# pressure_foot.net
KiCad netlist of a schematic drawn in EAGLE
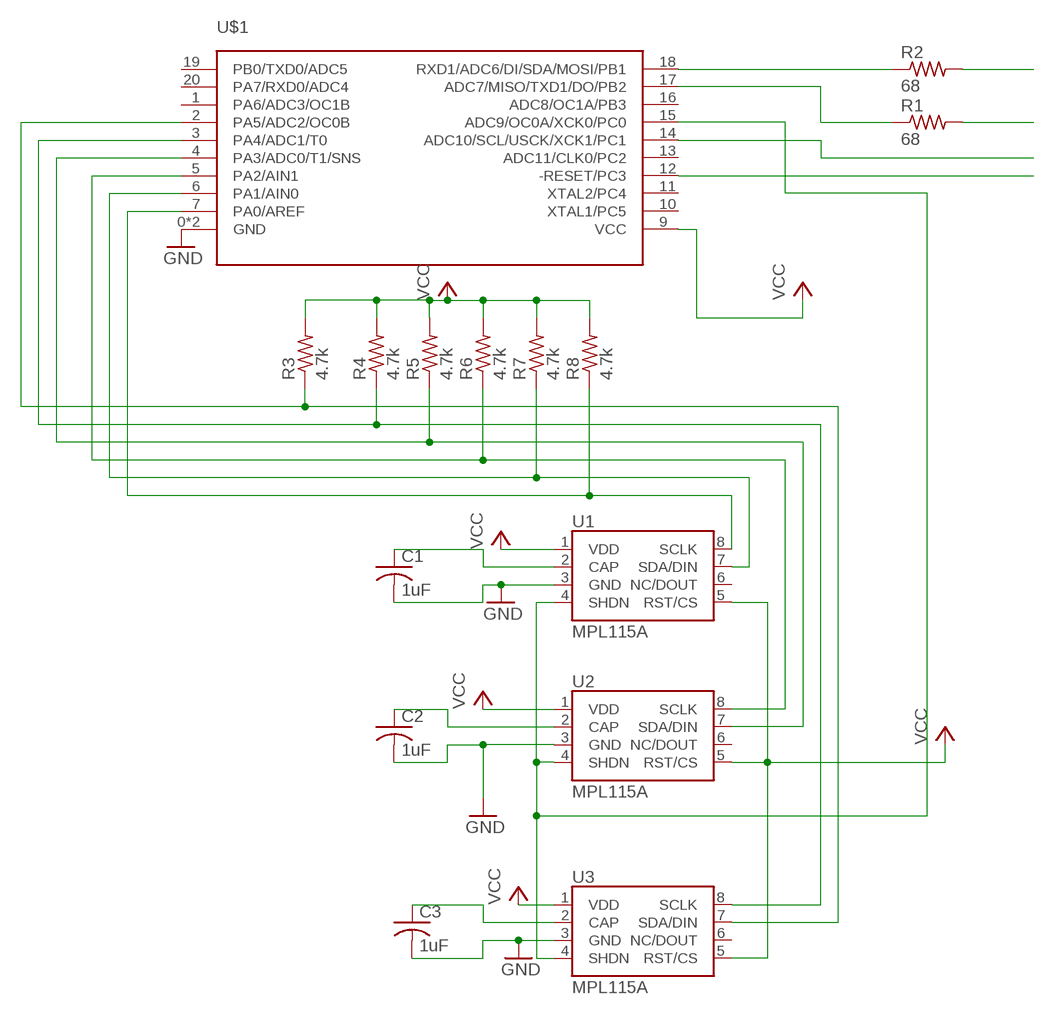
[diagram p0: schematic, sheet 1]

(export (version "E")
  (design (tool "Eeschema 10.0.6"))
  (components
    (comp (ref "C1")
      (value "1uF")
      (footprint "eagle-import:C0603")
      (libsource (lib "eagle-import") (part "C-USC0603"))
    )
    (comp (ref "C2")
      (value "1uF")
      (footprint "eagle-import:C0603")
      (libsource (lib "eagle-import") (part "C-USC0603"))
    )
    (comp (ref "C3")
      (value "1uF")
      (footprint "eagle-import:C0603")
      (libsource (lib "eagle-import") (part "C-USC0603"))
    )
    (comp (ref "R1")
      (value "68")
      (footprint "eagle-import:R0603")
      (libsource (lib "eagle-import") (part "R-US_R0603"))
    )
    (comp (ref "R2")
      (value "68")
      (footprint "eagle-import:R0603")
      (libsource (lib "eagle-import") (part "R-US_R0603"))
    )
    (comp (ref "R3")
      (value "4.7k")
      (footprint "eagle-import:R0603")
      (libsource (lib "eagle-import") (part "R-US_R0603"))
    )
    (comp (ref "R4")
      (value "4.7k")
      (footprint "eagle-import:R0603")
      (libsource (lib "eagle-import") (part "R-US_R0603"))
    )
    (comp (ref "R5")
      (value "4.7k")
      (footprint "eagle-import:R0603")
      (libsource (lib "eagle-import") (part "R-US_R0603"))
    )
    (comp (ref "R6")
      (value "4.7k")
      (footprint "eagle-import:R0603")
      (libsource (lib "eagle-import") (part "R-US_R0603"))
    )
    (comp (ref "R7")
      (value "4.7k")
      (footprint "eagle-import:R0603")
      (libsource (lib "eagle-import") (part "R-US_R0603"))
    )
    (comp (ref "R8")
      (value "4.7k")
      (footprint "eagle-import:R0603")
      (libsource (lib "eagle-import") (part "R-US_R0603"))
    )
    (comp (ref "U$1")
      (value "ATTINY1634QFN20")
      (footprint "eagle-import:QFN20")
      (libsource (lib "eagle-import") (part "ATTINY1634QFN20"))
    )
    (comp (ref "U1")
      (value "MPL115A")
      (footprint "eagle-import:LGA8")
      (libsource (lib "eagle-import") (part "MPL115A"))
    )
    (comp (ref "U2")
      (value "MPL115A")
      (footprint "eagle-import:LGA8")
      (libsource (lib "eagle-import") (part "MPL115A"))
    )
    (comp (ref "U3")
      (value "MPL115A")
      (footprint "eagle-import:LGA8")
      (libsource (lib "eagle-import") (part "MPL115A"))
    )
  )
  (nets
    (net (code "1") (name "GND") (class "Default")
      (node (ref "C1") (pin "2") (pinfunction "2_2") (pintype "passive"))
      (node (ref "C2") (pin "2") (pinfunction "2_2") (pintype "passive"))
      (node (ref "C3") (pin "2") (pinfunction "2_2") (pintype "passive"))
      (node (ref "U$1") (pin "0") (pinfunction "GND_0") (pintype "power_in"))
      (node (ref "U$1") (pin "8") (pinfunction "GND_8") (pintype "power_in"))
      (node (ref "U1") (pin "3") (pinfunction "GND_3") (pintype "bidirectional"))
      (node (ref "U2") (pin "3") (pinfunction "GND_3") (pintype "bidirectional"))
      (node (ref "U3") (pin "3") (pinfunction "GND_3") (pintype "bidirectional"))
    )
    (net (code "2") (name "Net-(U$1-ADC7{slash}MISO{slash}TXD1{slash}DO{slash}PB2)") (class "Default")
      (node (ref "R1") (pin "1") (pinfunction "1_1") (pintype "passive"))
      (node (ref "U$1") (pin "17") (pinfunction "ADC7/MISO/TXD1/DO/PB2_17") (pintype "bidirectional"))
    )
    (net (code "3") (name "Net-(U$1-ADC9{slash}OC0A{slash}XCK0{slash}PC0)") (class "Default")
      (node (ref "U$1") (pin "15") (pinfunction "ADC9/OC0A/XCK0/PC0_15") (pintype "bidirectional"))
      (node (ref "U1") (pin "4") (pinfunction "SHDN_4") (pintype "bidirectional"))
      (node (ref "U2") (pin "4") (pinfunction "SHDN_4") (pintype "bidirectional"))
      (node (ref "U3") (pin "4") (pinfunction "SHDN_4") (pintype "bidirectional"))
    )
    (net (code "4") (name "Net-(U$1-PA0{slash}AREF)") (class "Default")
      (node (ref "R8") (pin "1") (pinfunction "1_1") (pintype "passive"))
      (node (ref "U$1") (pin "7") (pinfunction "PA0/AREF_7") (pintype "bidirectional"))
      (node (ref "U1") (pin "8") (pinfunction "SCLK_8") (pintype "bidirectional"))
    )
    (net (code "5") (name "Net-(U$1-PA1{slash}AIN0)") (class "Default")
      (node (ref "R7") (pin "1") (pinfunction "1_1") (pintype "passive"))
      (node (ref "U$1") (pin "6") (pinfunction "PA1/AIN0_6") (pintype "bidirectional"))
      (node (ref "U1") (pin "7") (pinfunction "SDA/DIN_7") (pintype "bidirectional"))
    )
    (net (code "6") (name "Net-(U$1-PA2{slash}AIN1)") (class "Default")
      (node (ref "R6") (pin "1") (pinfunction "1_1") (pintype "passive"))
      (node (ref "U$1") (pin "5") (pinfunction "PA2/AIN1_5") (pintype "bidirectional"))
      (node (ref "U2") (pin "8") (pinfunction "SCLK_8") (pintype "bidirectional"))
    )
    (net (code "7") (name "Net-(U$1-PA3{slash}ADC0{slash}T1{slash}SNS)") (class "Default")
      (node (ref "R5") (pin "1") (pinfunction "1_1") (pintype "passive"))
      (node (ref "U$1") (pin "4") (pinfunction "PA3/ADC0/T1/SNS_4") (pintype "bidirectional"))
      (node (ref "U2") (pin "7") (pinfunction "SDA/DIN_7") (pintype "bidirectional"))
    )
    (net (code "8") (name "Net-(U$1-PA4{slash}ADC1{slash}T0)") (class "Default")
      (node (ref "R4") (pin "1") (pinfunction "1_1") (pintype "passive"))
      (node (ref "U$1") (pin "3") (pinfunction "PA4/ADC1/T0_3") (pintype "bidirectional"))
      (node (ref "U3") (pin "8") (pinfunction "SCLK_8") (pintype "bidirectional"))
    )
    (net (code "9") (name "Net-(U$1-PA5{slash}ADC2{slash}OC0B)") (class "Default")
      (node (ref "R3") (pin "1") (pinfunction "1_1") (pintype "passive"))
      (node (ref "U$1") (pin "2") (pinfunction "PA5/ADC2/OC0B_2") (pintype "bidirectional"))
      (node (ref "U3") (pin "7") (pinfunction "SDA/DIN_7") (pintype "bidirectional"))
    )
    (net (code "10") (name "Net-(U$1-RXD1{slash}ADC6{slash}DI{slash}SDA{slash}MOSI{slash}PB1)") (class "Default")
      (node (ref "R2") (pin "1") (pinfunction "1_1") (pintype "passive"))
      (node (ref "U$1") (pin "18") (pinfunction "RXD1/ADC6/DI/SDA/MOSI/PB1_18") (pintype "bidirectional"))
    )
    (net (code "11") (name "Net-(U1-CAP)") (class "Default")
      (node (ref "C1") (pin "1") (pinfunction "1_1") (pintype "passive"))
      (node (ref "U1") (pin "2") (pinfunction "CAP_2") (pintype "bidirectional"))
    )
    (net (code "12") (name "Net-(U2-CAP)") (class "Default")
      (node (ref "C2") (pin "1") (pinfunction "1_1") (pintype "passive"))
      (node (ref "U2") (pin "2") (pinfunction "CAP_2") (pintype "bidirectional"))
    )
    (net (code "13") (name "Net-(U3-CAP)") (class "Default")
      (node (ref "C3") (pin "1") (pinfunction "1_1") (pintype "passive"))
      (node (ref "U3") (pin "2") (pinfunction "CAP_2") (pintype "bidirectional"))
    )
    (net (code "14") (name "VCC") (class "Default")
      (node (ref "R3") (pin "2") (pinfunction "2_2") (pintype "passive"))
      (node (ref "R4") (pin "2") (pinfunction "2_2") (pintype "passive"))
      (node (ref "R5") (pin "2") (pinfunction "2_2") (pintype "passive"))
      (node (ref "R6") (pin "2") (pinfunction "2_2") (pintype "passive"))
      (node (ref "R7") (pin "2") (pinfunction "2_2") (pintype "passive"))
      (node (ref "R8") (pin "2") (pinfunction "2_2") (pintype "passive"))
      (node (ref "U$1") (pin "9") (pinfunction "VCC_9") (pintype "power_in"))
      (node (ref "U1") (pin "1") (pinfunction "VDD_1") (pintype "bidirectional"))
      (node (ref "U1") (pin "5") (pinfunction "RST/CS_5") (pintype "bidirectional"))
      (node (ref "U2") (pin "1") (pinfunction "VDD_1") (pintype "bidirectional"))
      (node (ref "U2") (pin "5") (pinfunction "RST/CS_5") (pintype "bidirectional"))
      (node (ref "U3") (pin "1") (pinfunction "VDD_1") (pintype "bidirectional"))
      (node (ref "U3") (pin "5") (pinfunction "RST/CS_5") (pintype "bidirectional"))
    )
    (net (code "15") (name "unconnected-(R1-Pad2)") (class "Default")
      (node (ref "R1") (pin "2") (pinfunction "2_2") (pintype "passive"))
    )
    (net (code "16") (name "unconnected-(R2-Pad2)") (class "Default")
      (node (ref "R2") (pin "2") (pinfunction "2_2") (pintype "passive"))
    )
    (net (code "17") (name "unconnected-(U$1--RESET{slash}PC3-Pad12)") (class "Default")
      (node (ref "U$1") (pin "12") (pinfunction "-RESET/PC3_12") (pintype "bidirectional"))
    )
    (net (code "18") (name "unconnected-(U$1-ADC8{slash}OC1A{slash}PB3-Pad16)") (class "Default")
      (node (ref "U$1") (pin "16") (pinfunction "ADC8/OC1A/PB3_16") (pintype "bidirectional"))
    )
    (net (code "19") (name "unconnected-(U$1-ADC10{slash}SCL{slash}USCK{slash}XCK1{slash}PC1-Pad14)") (class "Default")
      (node (ref "U$1") (pin "14") (pinfunction "ADC10/SCL/USCK/XCK1/PC1_14") (pintype "bidirectional"))
    )
    (net (code "20") (name "unconnected-(U$1-ADC11{slash}CLK0{slash}PC2-Pad13)") (class "Default")
      (node (ref "U$1") (pin "13") (pinfunction "ADC11/CLK0/PC2_13") (pintype "bidirectional"))
    )
    (net (code "21") (name "unconnected-(U$1-PA6{slash}ADC3{slash}OC1B-Pad1)") (class "Default")
      (node (ref "U$1") (pin "1") (pinfunction "PA6/ADC3/OC1B_1") (pintype "bidirectional"))
    )
    (net (code "22") (name "unconnected-(U$1-PA7{slash}RXD0{slash}ADC4-Pad20)") (class "Default")
      (node (ref "U$1") (pin "20") (pinfunction "PA7/RXD0/ADC4_20") (pintype "bidirectional"))
    )
    (net (code "23") (name "unconnected-(U$1-PB0{slash}TXD0{slash}ADC5-Pad19)") (class "Default")
      (node (ref "U$1") (pin "19") (pinfunction "PB0/TXD0/ADC5_19") (pintype "bidirectional"))
    )
    (net (code "24") (name "unconnected-(U$1-XTAL1{slash}PC5-Pad10)") (class "Default")
      (node (ref "U$1") (pin "10") (pinfunction "XTAL1/PC5_10") (pintype "bidirectional"))
    )
    (net (code "25") (name "unconnected-(U$1-XTAL2{slash}PC4-Pad11)") (class "Default")
      (node (ref "U$1") (pin "11") (pinfunction "XTAL2/PC4_11") (pintype "bidirectional"))
    )
    (net (code "26") (name "unconnected-(U1-NC{slash}DOUT-Pad6)") (class "Default")
      (node (ref "U1") (pin "6") (pinfunction "NC/DOUT_6") (pintype "bidirectional"))
    )
    (net (code "27") (name "unconnected-(U2-NC{slash}DOUT-Pad6)") (class "Default")
      (node (ref "U2") (pin "6") (pinfunction "NC/DOUT_6") (pintype "bidirectional"))
    )
    (net (code "28") (name "unconnected-(U3-NC{slash}DOUT-Pad6)") (class "Default")
      (node (ref "U3") (pin "6") (pinfunction "NC/DOUT_6") (pintype "bidirectional"))
    )
  )
)
